# Audio-HDMI.net
KiCad netlist of a schematic drawn in Altium Designer
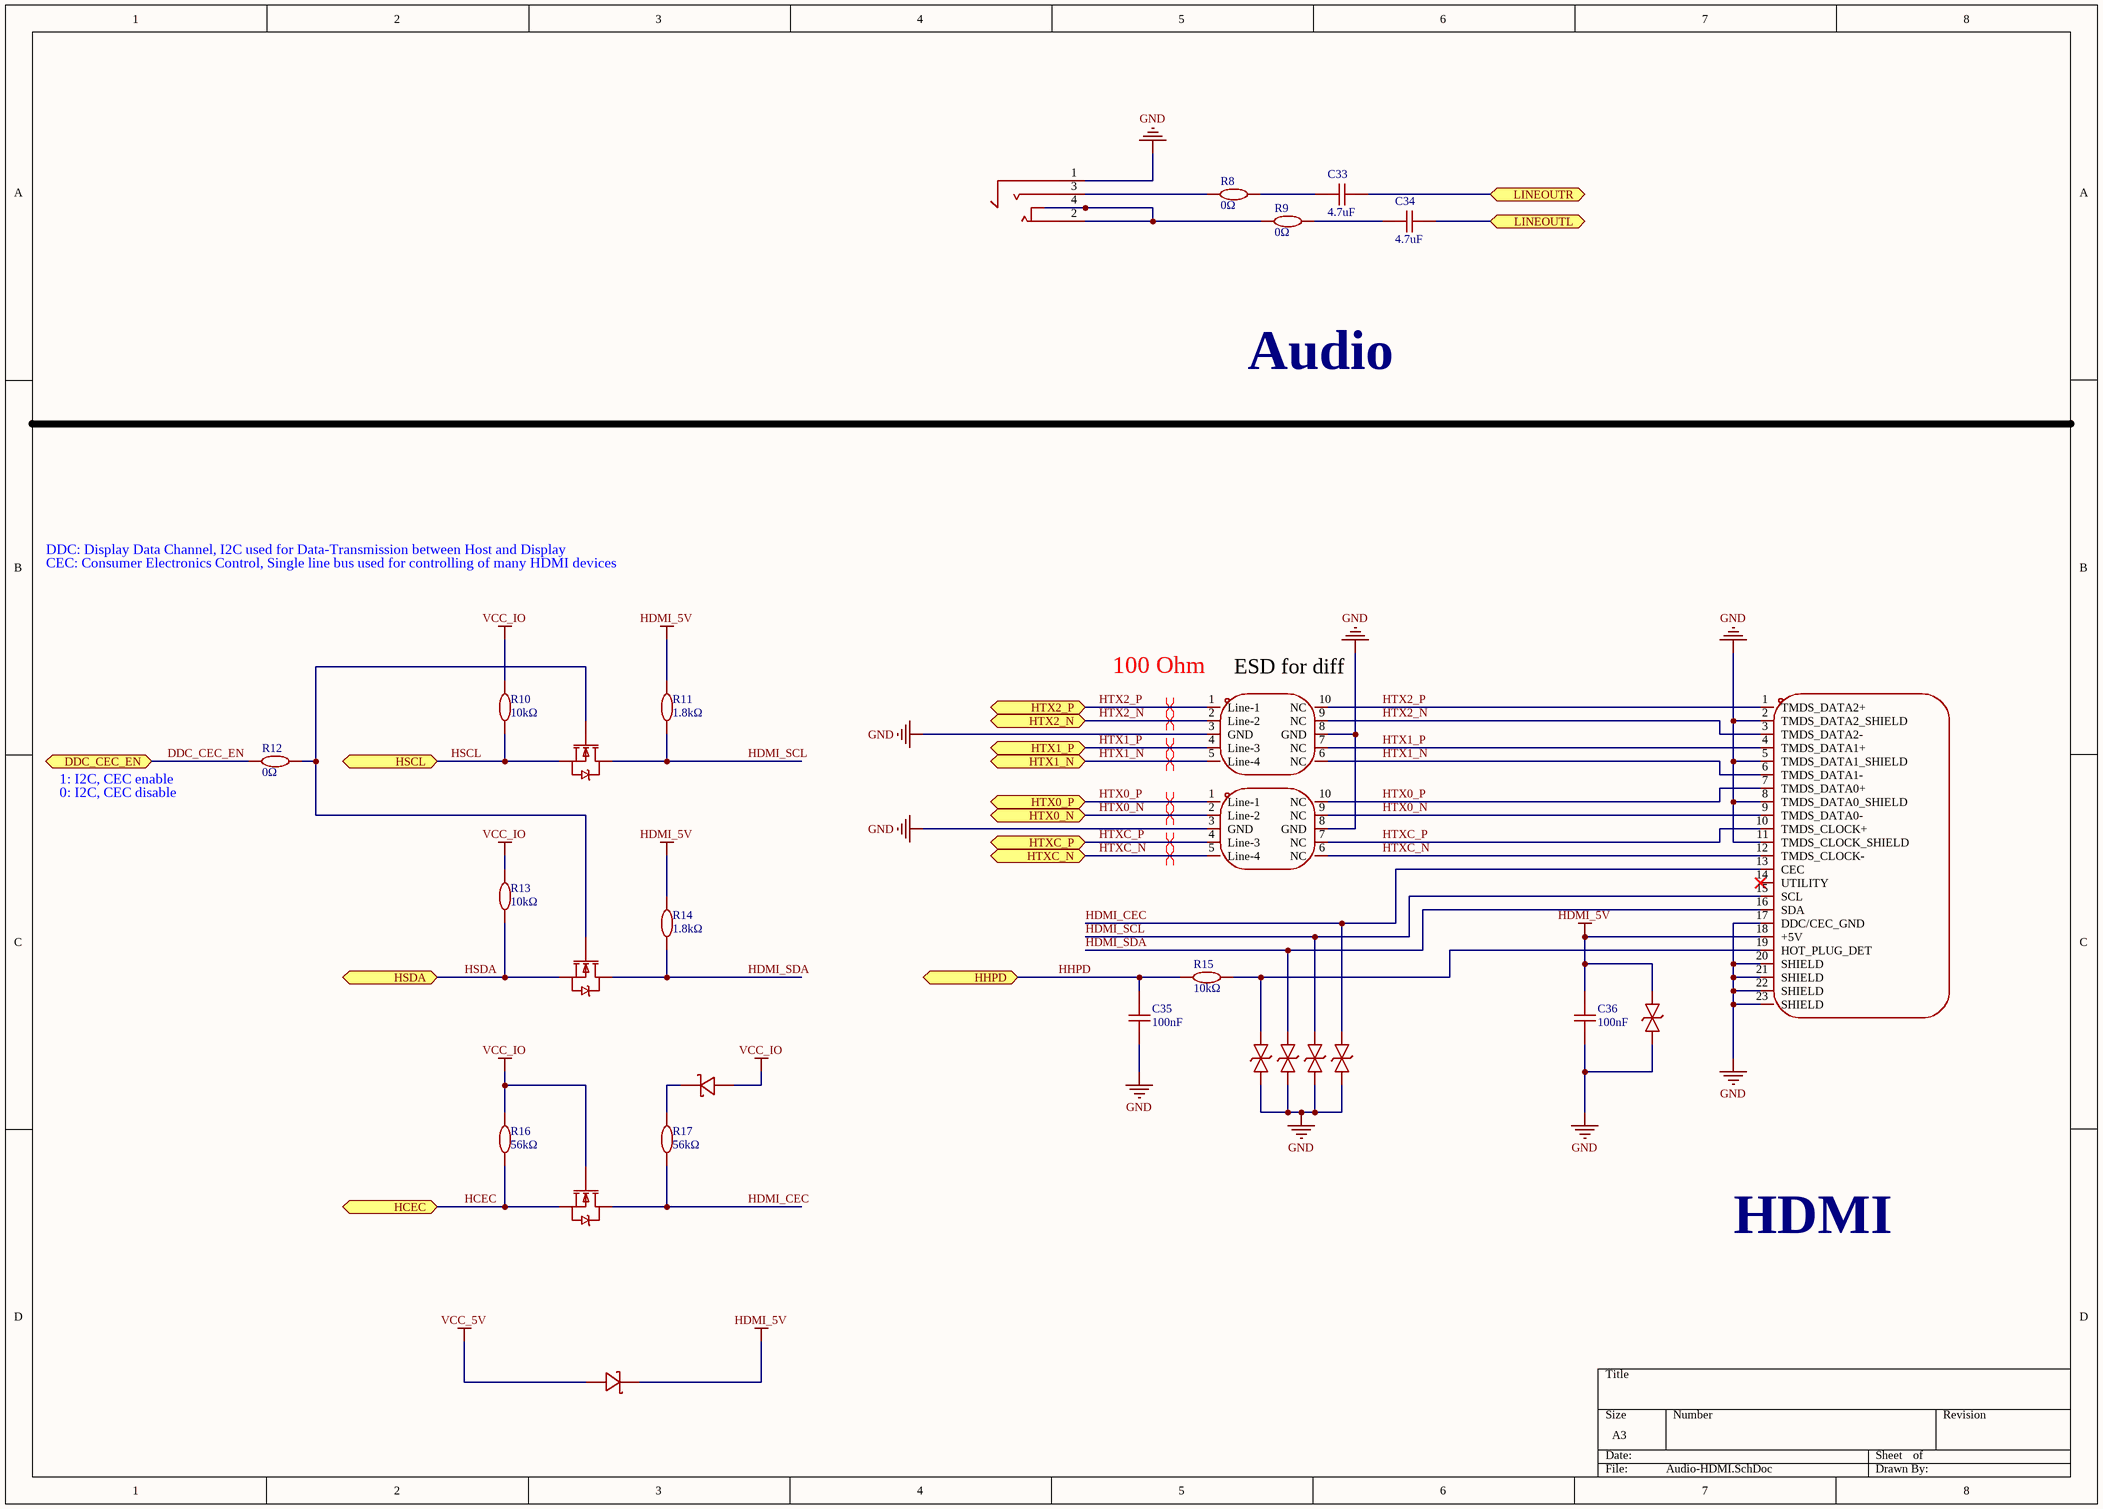
[diagram p0: Audio-HDMI.SchDoc]

(export (version "E")
  (design (tool "Eeschema 10.0.6"))
  (components
    (comp (ref "AUDIO1")
      (value "PJ-327C-4A")
      (footprint "AUDIO-SMD_PJ-327C-4A")
      (description "3.5mm Headphone Jack 30V 500mA SMD Audio Connectors ROHS")
      (fields (field (name "MANUFACTURER") "韩国韩荣"))
      (libsource (lib "IC") (part "PJ-327C-4A"))
    )
    (comp (ref "C33")
      (value "4.7uF")
      (footprint "C0402")
      (description "10V 4.7uF X5R ±20% 0402 Ceramic Capacitors ROHS")
      (libsource (lib "RLC") (part "4.7uF"))
    )
    (comp (ref "C34")
      (value "4.7uF")
      (footprint "C0402")
      (description "10V 4.7uF X5R ±20% 0402 Ceramic Capacitors ROHS")
      (libsource (lib "RLC") (part "4.7uF"))
    )
    (comp (ref "C35")
      (value "100nF")
      (footprint "C0402")
      (description "50V 100nF X7R ±10% 0402 Ceramic Capacitors ROHS")
      (libsource (lib "RLC") (part "100nF"))
    )
    (comp (ref "C36")
      (value "100nF")
      (footprint "C0402")
      (description "50V 100nF X7R ±10% 0402 Ceramic Capacitors ROHS")
      (libsource (lib "RLC") (part "100nF"))
    )
    (comp (ref "CN1")
      (value "KH-HDMI-19P-Cu")
      (footprint "HDMI-SMD_KH-HDMI-19P-CU")
      (description "HDMI-A SMD USB, DVI, HDMI Connector Assemblies ROHS")
      (fields (field (name "MANUFACTURER") "kinghelm(金航标)"))
      (libsource (lib "Connector") (part "KH-HDMI-19P-Cu"))
    )
    (comp (ref "D1")
      (value "AZ1045-04F.R7G")
      (footprint "DFN2510-10_L2.5-W1.0-P0.50-BL")
      (description "3.5A@8/20us 30W@8/20us 12V 6V 5V DFN2510-10 TVS Diodes ROHS")
      (fields (field (name "MANUFACTURER") "AMAZING(晶焱)"))
      (libsource (lib "IC") (part "AZ1045-04F.R7G"))
    )
    (comp (ref "D2")
      (value "AZ1045-04F.R7G")
      (footprint "DFN2510-10_L2.5-W1.0-P0.50-BL")
      (description "3.5A@8/20us 30W@8/20us 12V 6V 5V DFN2510-10 TVS Diodes ROHS")
      (fields (field (name "MANUFACTURER") "AMAZING(晶焱)"))
      (libsource (lib "IC") (part "AZ1045-04F.R7G"))
    )
    (comp (ref "D3")
      (value "1N5819WS")
      (footprint "SOD-323_L1.8-W1.3-LS2.5-RD")
      (description "25A 40V 600mV@1A 1A SOD-323 Single Diodes ROHS")
      (fields (field (name "MANUFACTURER") "Hottech(合科泰)"))
      (libsource (lib "LED") (part "1N5819WS_C191023"))
    )
    (comp (ref "D4")
      (value "1N5819WS")
      (footprint "SOD-323_L1.8-W1.3-LS2.5-RD")
      (description "25A 40V 600mV@1A 1A SOD-323 Single Diodes ROHS")
      (fields (field (name "MANUFACTURER") "Hottech(合科泰)"))
      (libsource (lib "LED") (part "1N5819WS_C191023"))
    )
    (comp (ref "Q1")
      (value "BSN20")
      (footprint "SOT-23-3_L2.9-W1.6-P1.90-LS2.8-BR")
      (description "50V 100mA 10Ω@2.75V,0.2A 1.5V@250uA 1 N-Channel SOT-23 Single FETs, MOSFETs ROHS")
      (fields (field (name "MANUFACTURER") "SHIKUES(时科)"))
      (libsource (lib "Transistor") (part "BSN20_C116157"))
    )
    (comp (ref "Q2")
      (value "BSN20")
      (footprint "SOT-23-3_L2.9-W1.6-P1.90-LS2.8-BR")
      (description "50V 100mA 10Ω@2.75V,0.2A 1.5V@250uA 1 N-Channel SOT-23 Single FETs, MOSFETs ROHS")
      (fields (field (name "MANUFACTURER") "SHIKUES(时科)"))
      (libsource (lib "Transistor") (part "BSN20_C116157"))
    )
    (comp (ref "Q3")
      (value "BSN20")
      (footprint "SOT-23-3_L2.9-W1.6-P1.90-LS2.8-BR")
      (description "50V 100mA 10Ω@2.75V,0.2A 1.5V@250uA 1 N-Channel SOT-23 Single FETs, MOSFETs ROHS")
      (fields (field (name "MANUFACTURER") "SHIKUES(时科)"))
      (libsource (lib "Transistor") (part "BSN20_C116157"))
    )
    (comp (ref "R8")
      (value "0Ω")
      (footprint "R0402")
      (description "0Ω 62.5mW 50V Thick Film Resistor ±1% 0402 Chip Resistor - Surface Mount ROHS")
      (libsource (lib "RLC") (part "0Ω"))
    )
    (comp (ref "R9")
      (value "0Ω")
      (footprint "R0402")
      (description "0Ω 62.5mW 50V Thick Film Resistor ±1% 0402 Chip Resistor - Surface Mount ROHS")
      (libsource (lib "RLC") (part "0Ω"))
    )
    (comp (ref "R10")
      (value "10kΩ")
      (footprint "R0402")
      (description "62.5mW 10kΩ 50V ±100ppm/℃ Thick Film Resistor ±1% 0402 Chip Resistor - Surface Mount ROHS")
      (libsource (lib "RLC") (part "10kΩ"))
    )
    (comp (ref "R11")
      (value "1.8kΩ")
      (footprint "R0402")
      (description "62.5mW 1.8kΩ 50V ±100ppm/℃ Thick Film Resistor ±1% 0402 Chip Resistor - Surface Mount ROHS")
      (libsource (lib "RLC") (part "1.8kΩ"))
    )
    (comp (ref "R12")
      (value "0Ω")
      (footprint "R0402")
      (description "0Ω 62.5mW 50V Thick Film Resistor ±1% 0402 Chip Resistor - Surface Mount ROHS")
      (libsource (lib "RLC") (part "0Ω"))
    )
    (comp (ref "R13")
      (value "10kΩ")
      (footprint "R0402")
      (description "62.5mW 10kΩ 50V ±100ppm/℃ Thick Film Resistor ±1% 0402 Chip Resistor - Surface Mount ROHS")
      (libsource (lib "RLC") (part "10kΩ"))
    )
    (comp (ref "R14")
      (value "1.8kΩ")
      (footprint "R0402")
      (description "62.5mW 1.8kΩ 50V ±100ppm/℃ Thick Film Resistor ±1% 0402 Chip Resistor - Surface Mount ROHS")
      (libsource (lib "RLC") (part "1.8kΩ"))
    )
    (comp (ref "R15")
      (value "10kΩ")
      (footprint "R0402")
      (description "62.5mW 10kΩ 50V ±100ppm/℃ Thick Film Resistor ±1% 0402 Chip Resistor - Surface Mount ROHS")
      (libsource (lib "RLC") (part "10kΩ"))
    )
    (comp (ref "R16")
      (value "56kΩ")
      (footprint "R0402")
      (description "56kΩ 62.5mW 50V ±100ppm/℃ Thick Film Resistor ±1% 0402 Chip Resistor - Surface Mount ROHS")
      (libsource (lib "RLC") (part "56kΩ"))
    )
    (comp (ref "R17")
      (value "56kΩ")
      (footprint "R0402")
      (description "56kΩ 62.5mW 50V ±100ppm/℃ Thick Film Resistor ±1% 0402 Chip Resistor - Surface Mount ROHS")
      (libsource (lib "RLC") (part "56kΩ"))
    )
    (comp (ref "U7")
      (value "ESD5451N")
      (footprint "DFN1006-2L-BI")
      (description "9A 9.8V 8V Bidirectional 5V DFN1006-2L TVS Diodes ROHS")
      (fields (field (name "MANUFACTURER") "HXY MOSFET(华轩阳电子)"))
      (libsource (lib "LED") (part "ESD5451N_C5261080"))
    )
    (comp (ref "U8")
      (value "ESD5451N")
      (footprint "DFN1006-2L-BI")
      (description "9A 9.8V 8V Bidirectional 5V DFN1006-2L TVS Diodes ROHS")
      (fields (field (name "MANUFACTURER") "HXY MOSFET(华轩阳电子)"))
      (libsource (lib "LED") (part "ESD5451N_C5261080"))
    )
    (comp (ref "U9")
      (value "ESD5451N")
      (footprint "DFN1006-2L-BI")
      (description "9A 9.8V 8V Bidirectional 5V DFN1006-2L TVS Diodes ROHS")
      (fields (field (name "MANUFACTURER") "HXY MOSFET(华轩阳电子)"))
      (libsource (lib "LED") (part "ESD5451N_C5261080"))
    )
    (comp (ref "U10")
      (value "ESD5451N")
      (footprint "DFN1006-2L-BI")
      (description "9A 9.8V 8V Bidirectional 5V DFN1006-2L TVS Diodes ROHS")
      (fields (field (name "MANUFACTURER") "HXY MOSFET(华轩阳电子)"))
      (libsource (lib "LED") (part "ESD5451N_C5261080"))
    )
    (comp (ref "U11")
      (value "ESD5451N")
      (footprint "DFN1006-2L-BI")
      (description "9A 9.8V 8V Bidirectional 5V DFN1006-2L TVS Diodes ROHS")
      (fields (field (name "MANUFACTURER") "HXY MOSFET(华轩阳电子)"))
      (libsource (lib "LED") (part "ESD5451N_C5261080"))
    )
  )
  (nets
    (net (code "1") (name "/DDC_CEC_EN") (class "Default")
      (node (ref "R12") (pin "1") (pinfunction "1_1") (pintype "passive"))
    )
    (net (code "2") (name "/HCEC") (class "Default")
      (node (ref "Q3") (pin "2") (pinfunction "S_2") (pintype "passive"))
      (node (ref "R16") (pin "1") (pinfunction "1_1") (pintype "passive"))
    )
    (net (code "3") (name "/HDMI_CEC") (class "Default")
      (node (ref "CN1") (pin "13") (pinfunction "CEC_13") (pintype "passive"))
      (node (ref "Q3") (pin "3") (pinfunction "D_3") (pintype "passive"))
      (node (ref "R17") (pin "1") (pinfunction "1_1") (pintype "passive"))
      (node (ref "U11") (pin "2") (pinfunction "2_2") (pintype "passive"))
    )
    (net (code "4") (name "/HDMI_SCL") (class "Default")
      (node (ref "CN1") (pin "15") (pinfunction "SCL_15") (pintype "passive"))
      (node (ref "Q1") (pin "3") (pinfunction "D_3") (pintype "passive"))
      (node (ref "R11") (pin "1") (pinfunction "1_1") (pintype "passive"))
      (node (ref "U10") (pin "2") (pinfunction "2_2") (pintype "passive"))
    )
    (net (code "5") (name "/HDMI_SDA") (class "Default")
      (node (ref "CN1") (pin "16") (pinfunction "SDA_16") (pintype "passive"))
      (node (ref "Q2") (pin "3") (pinfunction "D_3") (pintype "passive"))
      (node (ref "R14") (pin "1") (pinfunction "1_1") (pintype "passive"))
      (node (ref "U9") (pin "2") (pinfunction "2_2") (pintype "passive"))
    )
    (net (code "6") (name "/HHPD") (class "Default")
      (node (ref "C35") (pin "2") (pinfunction "2_2") (pintype "passive"))
      (node (ref "R15") (pin "1") (pinfunction "1_1") (pintype "passive"))
    )
    (net (code "7") (name "/HSCL") (class "Default")
      (node (ref "Q1") (pin "2") (pinfunction "S_2") (pintype "passive"))
      (node (ref "R10") (pin "1") (pinfunction "1_1") (pintype "passive"))
    )
    (net (code "8") (name "/HSDA") (class "Default")
      (node (ref "Q2") (pin "2") (pinfunction "S_2") (pintype "passive"))
      (node (ref "R13") (pin "1") (pinfunction "1_1") (pintype "passive"))
    )
    (net (code "9") (name "/HTX0_N") (class "Default")
      (node (ref "CN1") (pin "9") (pinfunction "TMDS_DATA0-_9") (pintype "passive"))
      (node (ref "D2") (pin "2") (pinfunction "Line-2_2") (pintype "passive"))
      (node (ref "D2") (pin "9") (pinfunction "NC_9") (pintype "passive"))
    )
    (net (code "10") (name "/HTX0_P") (class "Default")
      (node (ref "CN1") (pin "7") (pinfunction "TMDS_DATA0+_7") (pintype "passive"))
      (node (ref "D2") (pin "1") (pinfunction "Line-1_1") (pintype "passive"))
      (node (ref "D2") (pin "10") (pinfunction "NC_10") (pintype "passive"))
    )
    (net (code "11") (name "/HTX1_N") (class "Default")
      (node (ref "CN1") (pin "6") (pinfunction "TMDS_DATA1-_6") (pintype "passive"))
      (node (ref "D1") (pin "5") (pinfunction "Line-4_5") (pintype "passive"))
      (node (ref "D1") (pin "6") (pinfunction "NC_6") (pintype "passive"))
    )
    (net (code "12") (name "/HTX1_P") (class "Default")
      (node (ref "CN1") (pin "4") (pinfunction "TMDS_DATA1+_4") (pintype "passive"))
      (node (ref "D1") (pin "4") (pinfunction "Line-3_4") (pintype "passive"))
      (node (ref "D1") (pin "7") (pinfunction "NC_7") (pintype "passive"))
    )
    (net (code "13") (name "/HTX2_N") (class "Default")
      (node (ref "CN1") (pin "3") (pinfunction "TMDS_DATA2-_3") (pintype "passive"))
      (node (ref "D1") (pin "2") (pinfunction "Line-2_2") (pintype "passive"))
      (node (ref "D1") (pin "9") (pinfunction "NC_9") (pintype "passive"))
    )
    (net (code "14") (name "/HTX2_P") (class "Default")
      (node (ref "CN1") (pin "1") (pinfunction "TMDS_DATA2+_1") (pintype "passive"))
      (node (ref "D1") (pin "1") (pinfunction "Line-1_1") (pintype "passive"))
      (node (ref "D1") (pin "10") (pinfunction "NC_10") (pintype "passive"))
    )
    (net (code "15") (name "/HTXC_N") (class "Default")
      (node (ref "CN1") (pin "12") (pinfunction "TMDS_CLOCK-_12") (pintype "passive"))
      (node (ref "D2") (pin "5") (pinfunction "Line-4_5") (pintype "passive"))
      (node (ref "D2") (pin "6") (pinfunction "NC_6") (pintype "passive"))
    )
    (net (code "16") (name "/HTXC_P") (class "Default")
      (node (ref "CN1") (pin "10") (pinfunction "TMDS_CLOCK+_10") (pintype "passive"))
      (node (ref "D2") (pin "4") (pinfunction "Line-3_4") (pintype "passive"))
      (node (ref "D2") (pin "7") (pinfunction "NC_7") (pintype "passive"))
    )
    (net (code "17") (name "/LINEOUTL") (class "Default")
      (node (ref "C34") (pin "2") (pinfunction "2_2") (pintype "passive"))
    )
    (net (code "18") (name "/LINEOUTR") (class "Default")
      (node (ref "C33") (pin "2") (pinfunction "2_2") (pintype "passive"))
    )
    (net (code "19") (name "GND") (class "Default")
      (node (ref "AUDIO1") (pin "1") (pinfunction "1_1") (pintype "passive"))
      (node (ref "C35") (pin "1") (pinfunction "1_1") (pintype "passive"))
      (node (ref "C36") (pin "1") (pinfunction "1_1") (pintype "passive"))
      (node (ref "CN1") (pin "11") (pinfunction "TMDS_CLOCK_SHIELD_11") (pintype "passive"))
      (node (ref "CN1") (pin "17") (pinfunction "DDC/CEC_GND_17") (pintype "passive"))
      (node (ref "CN1") (pin "2") (pinfunction "TMDS_DATA2_SHIELD_2") (pintype "passive"))
      (node (ref "CN1") (pin "20") (pinfunction "SHIELD_20") (pintype "passive"))
      (node (ref "CN1") (pin "21") (pinfunction "SHIELD_21") (pintype "passive"))
      (node (ref "CN1") (pin "22") (pinfunction "SHIELD_22") (pintype "passive"))
      (node (ref "CN1") (pin "23") (pinfunction "SHIELD_23") (pintype "passive"))
      (node (ref "CN1") (pin "5") (pinfunction "TMDS_DATA1_SHIELD_5") (pintype "passive"))
      (node (ref "CN1") (pin "8") (pinfunction "TMDS_DATA0_SHIELD_8") (pintype "passive"))
      (node (ref "D1") (pin "3") (pinfunction "GND_3") (pintype "passive"))
      (node (ref "D1") (pin "8") (pinfunction "GND_8") (pintype "passive"))
      (node (ref "D2") (pin "3") (pinfunction "GND_3") (pintype "passive"))
      (node (ref "D2") (pin "8") (pinfunction "GND_8") (pintype "passive"))
      (node (ref "U10") (pin "1") (pinfunction "1_1") (pintype "passive"))
      (node (ref "U11") (pin "1") (pinfunction "1_1") (pintype "passive"))
      (node (ref "U7") (pin "1") (pinfunction "1_1") (pintype "passive"))
      (node (ref "U8") (pin "1") (pinfunction "1_1") (pintype "passive"))
      (node (ref "U9") (pin "1") (pinfunction "1_1") (pintype "passive"))
    )
    (net (code "20") (name "HDMI_5V") (class "Default")
      (node (ref "C36") (pin "2") (pinfunction "2_2") (pintype "passive"))
      (node (ref "CN1") (pin "18") (pinfunction "+5V_18") (pintype "passive"))
      (node (ref "D4") (pin "1") (pinfunction "K_1") (pintype "passive"))
      (node (ref "R11") (pin "2") (pinfunction "2_2") (pintype "passive"))
      (node (ref "R14") (pin "2") (pinfunction "2_2") (pintype "passive"))
      (node (ref "U7") (pin "2") (pinfunction "2_2") (pintype "passive"))
    )
    (net (code "21") (name "Net-(AUDIO1-Pad2)") (class "Default")
      (node (ref "AUDIO1") (pin "2") (pinfunction "2_2") (pintype "passive"))
      (node (ref "AUDIO1") (pin "4") (pinfunction "4_4") (pintype "passive"))
      (node (ref "R9") (pin "1") (pinfunction "1_1") (pintype "passive"))
    )
    (net (code "22") (name "Net-(AUDIO1-Pad3)") (class "Default")
      (node (ref "AUDIO1") (pin "3") (pinfunction "3_3") (pintype "passive"))
      (node (ref "R8") (pin "1") (pinfunction "1_1") (pintype "passive"))
    )
    (net (code "23") (name "Net-(C33-Pad1)") (class "Default")
      (node (ref "C33") (pin "1") (pinfunction "1_1") (pintype "passive"))
      (node (ref "R8") (pin "2") (pinfunction "2_2") (pintype "passive"))
    )
    (net (code "24") (name "Net-(C34-Pad1)") (class "Default")
      (node (ref "C34") (pin "1") (pinfunction "1_1") (pintype "passive"))
      (node (ref "R9") (pin "2") (pinfunction "2_2") (pintype "passive"))
    )
    (net (code "25") (name "Net-(CN1-HOT_PLUG_DET)") (class "Default")
      (node (ref "CN1") (pin "19") (pinfunction "HOT_PLUG_DET_19") (pintype "passive"))
      (node (ref "R15") (pin "2") (pinfunction "2_2") (pintype "passive"))
      (node (ref "U8") (pin "2") (pinfunction "2_2") (pintype "passive"))
    )
    (net (code "26") (name "Net-(D3-K)") (class "Default")
      (node (ref "D3") (pin "1") (pinfunction "K_1") (pintype "passive"))
      (node (ref "R17") (pin "2") (pinfunction "2_2") (pintype "passive"))
    )
    (net (code "27") (name "Net-(Q1-G)") (class "Default")
      (node (ref "Q1") (pin "1") (pinfunction "G_1") (pintype "passive"))
      (node (ref "Q2") (pin "1") (pinfunction "G_1") (pintype "passive"))
      (node (ref "R12") (pin "2") (pinfunction "2_2") (pintype "passive"))
    )
    (net (code "28") (name "VCC_5V") (class "Default")
      (node (ref "D4") (pin "2") (pinfunction "A_2") (pintype "passive"))
    )
    (net (code "29") (name "VCC_IO") (class "Default")
      (node (ref "D3") (pin "2") (pinfunction "A_2") (pintype "passive"))
      (node (ref "Q3") (pin "1") (pinfunction "G_1") (pintype "passive"))
      (node (ref "R10") (pin "2") (pinfunction "2_2") (pintype "passive"))
      (node (ref "R13") (pin "2") (pinfunction "2_2") (pintype "passive"))
      (node (ref "R16") (pin "2") (pinfunction "2_2") (pintype "passive"))
    )
    (net (code "30") (name "unconnected-(CN1-UTILITY-Pad14)") (class "Default")
      (node (ref "CN1") (pin "14") (pinfunction "UTILITY_14") (pintype "passive+no_connect"))
    )
  )
)
